# fb20-5.net
KiCad netlist of a schematic drawn in EAGLE
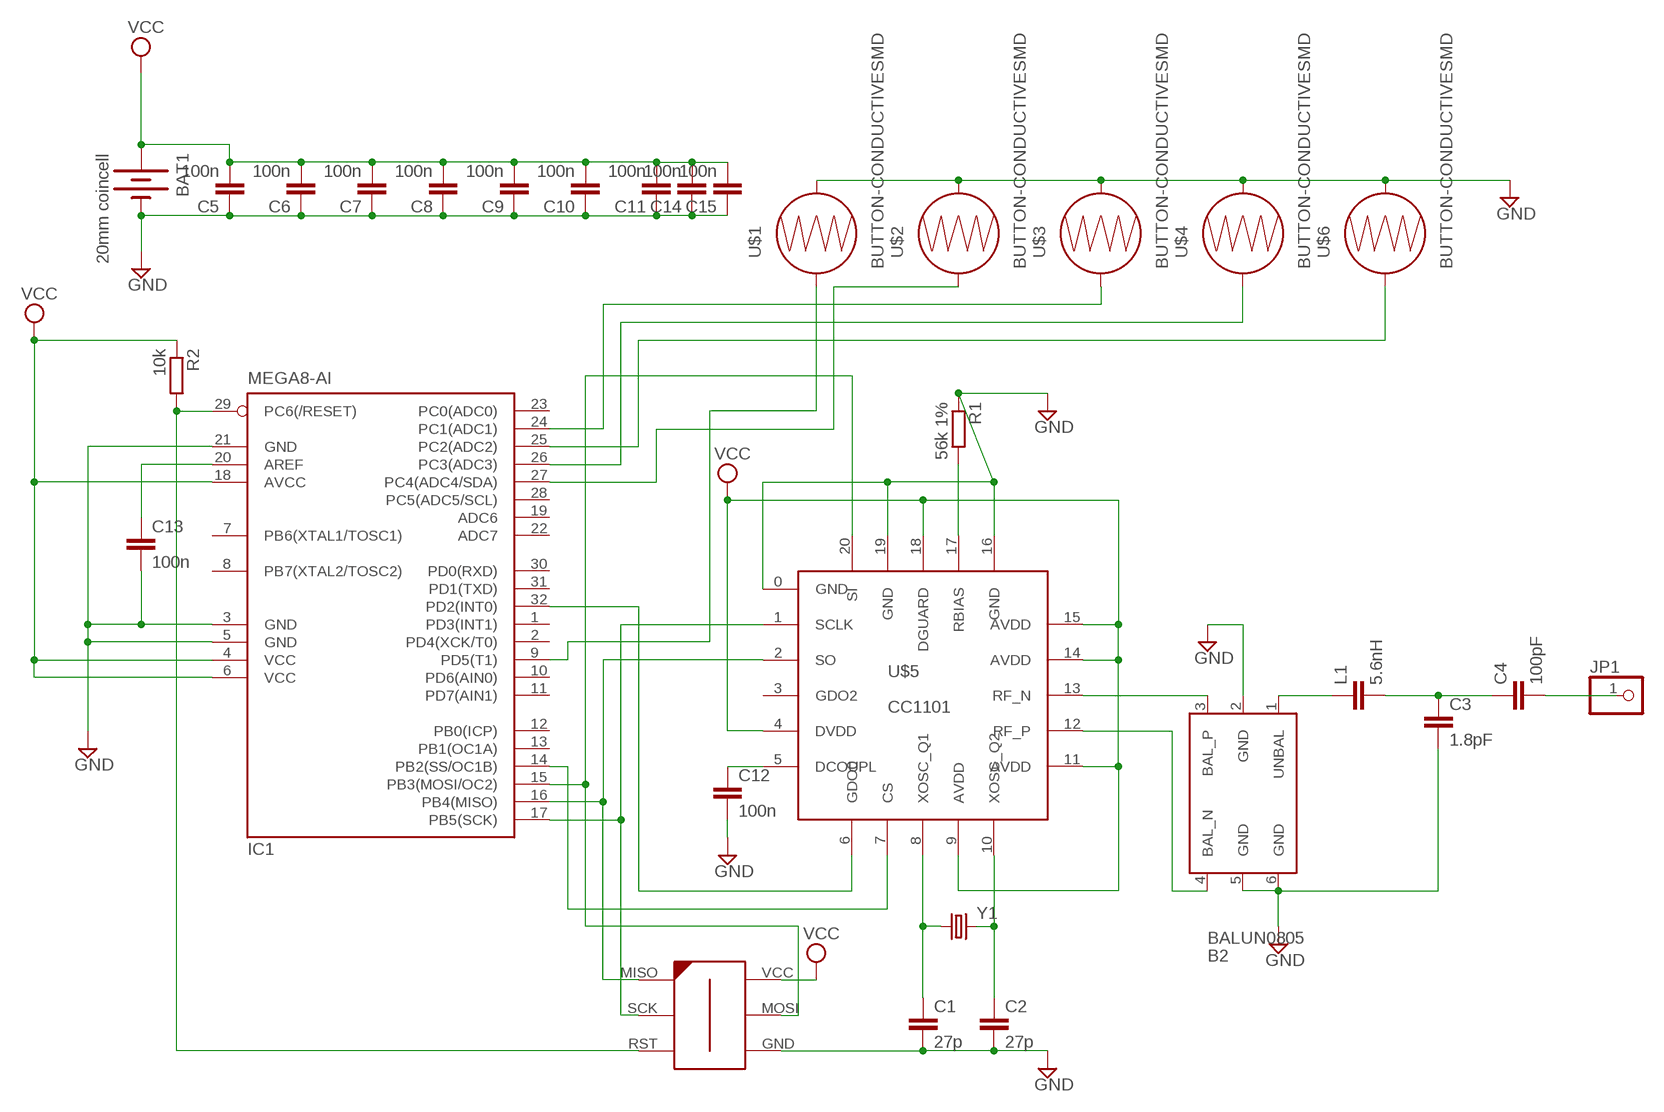
[diagram p0: schematic, sheet 1]

(export (version "E")
  (design (tool "Eeschema 10.0.6"))
  (components
    (comp (ref "B2")
      (value "BALUN0805")
      (footprint "eagle-import:BALUN")
      (libsource (lib "eagle-import") (part "BALUN0805"))
    )
    (comp (ref "BAT1")
      (value "20mm coincell")
      (footprint "eagle-import:BATTCON_20MM_4LEGS")
      (libsource (lib "eagle-import") (part "BATTERY20MM_4LEGS"))
    )
    (comp (ref "C1")
      (value "27p")
      (footprint "eagle-import:C0402")
      (libsource (lib "eagle-import") (part "C-EUC0402"))
    )
    (comp (ref "C2")
      (value "27p")
      (footprint "eagle-import:C0402")
      (libsource (lib "eagle-import") (part "C-EUC0402"))
    )
    (comp (ref "C3")
      (value "1.8pF")
      (footprint "eagle-import:C0402")
      (libsource (lib "eagle-import") (part "C-EUC0402"))
    )
    (comp (ref "C4")
      (value "100pF")
      (footprint "eagle-import:C0402")
      (libsource (lib "eagle-import") (part "C-EUC0402"))
    )
    (comp (ref "C5")
      (value "100n")
      (footprint "eagle-import:C0402")
      (libsource (lib "eagle-import") (part "C-EUC0402"))
    )
    (comp (ref "C6")
      (value "100n")
      (footprint "eagle-import:C0402")
      (libsource (lib "eagle-import") (part "C-EUC0402"))
    )
    (comp (ref "C7")
      (value "100n")
      (footprint "eagle-import:C0402")
      (libsource (lib "eagle-import") (part "C-EUC0402"))
    )
    (comp (ref "C8")
      (value "100n")
      (footprint "eagle-import:C0402")
      (libsource (lib "eagle-import") (part "C-EUC0402"))
    )
    (comp (ref "C9")
      (value "100n")
      (footprint "eagle-import:C0402")
      (libsource (lib "eagle-import") (part "C-EUC0402"))
    )
    (comp (ref "C10")
      (value "100n")
      (footprint "eagle-import:C0402")
      (libsource (lib "eagle-import") (part "C-EUC0402"))
    )
    (comp (ref "C11")
      (value "100n")
      (footprint "eagle-import:C0402")
      (libsource (lib "eagle-import") (part "C-EUC0402"))
    )
    (comp (ref "C12")
      (value "100n")
      (footprint "eagle-import:C0402")
      (libsource (lib "eagle-import") (part "C-EUC0402"))
    )
    (comp (ref "C13")
      (value "100n")
      (footprint "eagle-import:C0402")
      (libsource (lib "eagle-import") (part "C-EUC0402"))
    )
    (comp (ref "C14")
      (value "100n")
      (footprint "eagle-import:C0402")
      (libsource (lib "eagle-import") (part "C-EUC0402"))
    )
    (comp (ref "C15")
      (value "100n")
      (footprint "eagle-import:C0402")
      (libsource (lib "eagle-import") (part "C-EUC0402"))
    )
    (comp (ref "IC1")
      (value "MEGA8-AI")
      (footprint "eagle-import:TQFP32-08")
      (fields (field (name "MPN") "ATMEGA8-16AU"))
      (libsource (lib "eagle-import") (part "MEGA8-AI"))
    )
    (comp (ref "JP1")
      (value "PINHD-1X1")
      (footprint "eagle-import:1X01")
      (libsource (lib "eagle-import") (part "PINHD-1X1"))
    )
    (comp (ref "L1")
      (value "5.6nH")
      (footprint "eagle-import:C0603")
      (libsource (lib "eagle-import") (part "C-EUC0603"))
    )
    (comp (ref "R1")
      (value "56k 1%")
      (footprint "eagle-import:R0402")
      (libsource (lib "eagle-import") (part "R-EU_R0402"))
    )
    (comp (ref "R2")
      (value "10k")
      (footprint "eagle-import:R0402")
      (libsource (lib "eagle-import") (part "R-EU_R0402"))
    )
    (comp (ref "U$1")
      (value "BUTTON-CONDUCTIVESMD")
      (footprint "eagle-import:BUTTON-CONDUCTIVE")
      (libsource (lib "eagle-import") (part "BUTTON-CONDUCTIVESMD"))
    )
    (comp (ref "U$2")
      (value "BUTTON-CONDUCTIVESMD")
      (footprint "eagle-import:BUTTON-CONDUCTIVE")
      (libsource (lib "eagle-import") (part "BUTTON-CONDUCTIVESMD"))
    )
    (comp (ref "U$3")
      (value "BUTTON-CONDUCTIVESMD")
      (footprint "eagle-import:BUTTON-CONDUCTIVE")
      (libsource (lib "eagle-import") (part "BUTTON-CONDUCTIVESMD"))
    )
    (comp (ref "U$4")
      (value "BUTTON-CONDUCTIVESMD")
      (footprint "eagle-import:BUTTON-CONDUCTIVE")
      (libsource (lib "eagle-import") (part "BUTTON-CONDUCTIVESMD"))
    )
    (comp (ref "U$5")
      (value "CC1101")
      (footprint "eagle-import:QFN20")
      (libsource (lib "eagle-import") (part "CC1101"))
    )
    (comp (ref "U$6")
      (value "BUTTON-CONDUCTIVESMD")
      (footprint "eagle-import:BUTTON-CONDUCTIVE")
      (libsource (lib "eagle-import") (part "BUTTON-CONDUCTIVESMD"))
    )
    (comp (ref "U$7")
      (value "AVR-ISP-6-EDGE")
      (footprint "eagle-import:6PAD_ISP")
      (libsource (lib "eagle-import") (part "AVR-ISP-6-EDGE"))
    )
    (comp (ref "Y1")
      (value "CRYSTAL5X3")
      (footprint "eagle-import:CRYSTAL-SMD-5X3")
      (libsource (lib "eagle-import") (part "CRYSTAL5X3"))
    )
  )
  (nets
    (net (code "1") (name "GND") (class "Default")
      (node (ref "B2") (pin "2") (pinfunction "GND_2") (pintype "bidirectional"))
      (node (ref "B2") (pin "5") (pinfunction "GND_5") (pintype "bidirectional"))
      (node (ref "B2") (pin "6") (pinfunction "GND_6") (pintype "bidirectional"))
      (node (ref "BAT1") (pin "2") (pinfunction "-_2") (pintype "power_in"))
      (node (ref "C1") (pin "2") (pinfunction "2_2") (pintype "passive"))
      (node (ref "C10") (pin "1") (pinfunction "1_1") (pintype "passive"))
      (node (ref "C11") (pin "1") (pinfunction "1_1") (pintype "passive"))
      (node (ref "C12") (pin "2") (pinfunction "2_2") (pintype "passive"))
      (node (ref "C13") (pin "2") (pinfunction "2_2") (pintype "passive"))
      (node (ref "C14") (pin "1") (pinfunction "1_1") (pintype "passive"))
      (node (ref "C15") (pin "1") (pinfunction "1_1") (pintype "passive"))
      (node (ref "C2") (pin "2") (pinfunction "2_2") (pintype "passive"))
      (node (ref "C3") (pin "2") (pinfunction "2_2") (pintype "passive"))
      (node (ref "C5") (pin "1") (pinfunction "1_1") (pintype "passive"))
      (node (ref "C6") (pin "1") (pinfunction "1_1") (pintype "passive"))
      (node (ref "C7") (pin "1") (pinfunction "1_1") (pintype "passive"))
      (node (ref "C8") (pin "1") (pinfunction "1_1") (pintype "passive"))
      (node (ref "C9") (pin "1") (pinfunction "1_1") (pintype "passive"))
      (node (ref "IC1") (pin "21") (pinfunction "GND_21") (pintype "power_in"))
      (node (ref "IC1") (pin "3") (pinfunction "GND_3") (pintype "power_in"))
      (node (ref "IC1") (pin "5") (pinfunction "GND_5") (pintype "power_in"))
      (node (ref "R1") (pin "1") (pinfunction "1_1") (pintype "passive"))
      (node (ref "U$1") (pin "2") (pinfunction "2_2") (pintype "passive"))
      (node (ref "U$2") (pin "2") (pinfunction "2_2") (pintype "passive"))
      (node (ref "U$3") (pin "2") (pinfunction "2_2") (pintype "passive"))
      (node (ref "U$4") (pin "2") (pinfunction "2_2") (pintype "passive"))
      (node (ref "U$5") (pin "0") (pinfunction "GND_0") (pintype "bidirectional"))
      (node (ref "U$5") (pin "16") (pinfunction "GND_16") (pintype "bidirectional"))
      (node (ref "U$5") (pin "19") (pinfunction "GND_19") (pintype "bidirectional"))
      (node (ref "U$6") (pin "2") (pinfunction "2_2") (pintype "passive"))
      (node (ref "U$7") (pin "GND") (pinfunction "P$4_GND") (pintype "bidirectional"))
    )
    (net (code "2") (name "Net-(B2-BAL_N)") (class "Default")
      (node (ref "B2") (pin "4") (pinfunction "BAL_N_4") (pintype "bidirectional"))
      (node (ref "U$5") (pin "12") (pinfunction "RF_P_12") (pintype "bidirectional"))
    )
    (net (code "3") (name "Net-(B2-BAL_P)") (class "Default")
      (node (ref "B2") (pin "3") (pinfunction "BAL_P_3") (pintype "bidirectional"))
      (node (ref "U$5") (pin "13") (pinfunction "RF_N_13") (pintype "bidirectional"))
    )
    (net (code "4") (name "Net-(B2-UNBAL)") (class "Default")
      (node (ref "B2") (pin "1") (pinfunction "UNBAL_1") (pintype "bidirectional"))
      (node (ref "L1") (pin "1") (pinfunction "1_1") (pintype "passive"))
    )
    (net (code "5") (name "Net-(C3-Pad1)") (class "Default")
      (node (ref "C3") (pin "1") (pinfunction "1_1") (pintype "passive"))
      (node (ref "C4") (pin "1") (pinfunction "1_1") (pintype "passive"))
      (node (ref "L1") (pin "2") (pinfunction "2_2") (pintype "passive"))
    )
    (net (code "6") (name "Net-(C4-Pad2)") (class "Default")
      (node (ref "C4") (pin "2") (pinfunction "2_2") (pintype "passive"))
      (node (ref "JP1") (pin "1") (pinfunction "1_1") (pintype "passive"))
    )
    (net (code "7") (name "Net-(IC1-AREF)") (class "Default")
      (node (ref "C13") (pin "1") (pinfunction "1_1") (pintype "passive"))
      (node (ref "IC1") (pin "20") (pinfunction "AREF_20") (pintype "passive"))
    )
    (net (code "8") (name "Net-(IC1-PB2(SS{slash}OC1B))") (class "Default")
      (node (ref "IC1") (pin "14") (pinfunction "PB2(SS/OC1B)_14") (pintype "bidirectional"))
      (node (ref "U$5") (pin "7") (pinfunction "CS_7") (pintype "bidirectional"))
    )
    (net (code "9") (name "Net-(IC1-PB3(MOSI{slash}OC2))") (class "Default")
      (node (ref "IC1") (pin "15") (pinfunction "PB3(MOSI/OC2)_15") (pintype "bidirectional"))
      (node (ref "U$5") (pin "20") (pinfunction "SI_20") (pintype "bidirectional"))
      (node (ref "U$7") (pin "MOSI") (pinfunction "P$5_MOSI") (pintype "bidirectional"))
    )
    (net (code "10") (name "Net-(IC1-PB4(MISO))") (class "Default")
      (node (ref "IC1") (pin "16") (pinfunction "PB4(MISO)_16") (pintype "bidirectional"))
      (node (ref "U$5") (pin "2") (pinfunction "SO_2") (pintype "bidirectional"))
      (node (ref "U$7") (pin "MISO") (pinfunction "P$1_MISO") (pintype "bidirectional"))
    )
    (net (code "11") (name "Net-(IC1-PB5(SCK))") (class "Default")
      (node (ref "IC1") (pin "17") (pinfunction "PB5(SCK)_17") (pintype "bidirectional"))
      (node (ref "U$5") (pin "1") (pinfunction "SCLK_1") (pintype "bidirectional"))
      (node (ref "U$7") (pin "SCK") (pinfunction "P$2_SCK") (pintype "bidirectional"))
    )
    (net (code "12") (name "Net-(IC1-PC1(ADC1))") (class "Default")
      (node (ref "IC1") (pin "24") (pinfunction "PC1(ADC1)_24") (pintype "bidirectional"))
      (node (ref "U$3") (pin "1") (pinfunction "1_1") (pintype "passive"))
    )
    (net (code "13") (name "Net-(IC1-PC2(ADC2))") (class "Default")
      (node (ref "IC1") (pin "25") (pinfunction "PC2(ADC2)_25") (pintype "bidirectional"))
      (node (ref "U$6") (pin "1") (pinfunction "1_1") (pintype "passive"))
    )
    (net (code "14") (name "Net-(IC1-PC3(ADC3))") (class "Default")
      (node (ref "IC1") (pin "26") (pinfunction "PC3(ADC3)_26") (pintype "bidirectional"))
      (node (ref "U$4") (pin "1") (pinfunction "1_1") (pintype "passive"))
    )
    (net (code "15") (name "Net-(IC1-PC4(ADC4{slash}SDA))") (class "Default")
      (node (ref "IC1") (pin "27") (pinfunction "PC4(ADC4/SDA)_27") (pintype "bidirectional"))
      (node (ref "U$2") (pin "1") (pinfunction "1_1") (pintype "passive"))
    )
    (net (code "16") (name "Net-(IC1-PC6({slash}RESET))") (class "Default")
      (node (ref "IC1") (pin "29") (pinfunction "PC6(/RESET)_29") (pintype "bidirectional"))
      (node (ref "R2") (pin "2") (pinfunction "2_2") (pintype "passive"))
      (node (ref "U$7") (pin "RST") (pinfunction "P$3_RST") (pintype "bidirectional"))
    )
    (net (code "17") (name "Net-(IC1-PD2(INT0))") (class "Default")
      (node (ref "IC1") (pin "32") (pinfunction "PD2(INT0)_32") (pintype "bidirectional"))
      (node (ref "U$5") (pin "6") (pinfunction "GDO0_6") (pintype "bidirectional"))
    )
    (net (code "18") (name "Net-(IC1-PD5(T1))") (class "Default")
      (node (ref "IC1") (pin "9") (pinfunction "PD5(T1)_9") (pintype "bidirectional"))
      (node (ref "U$1") (pin "1") (pinfunction "1_1") (pintype "passive"))
    )
    (net (code "19") (name "Net-(U$5-DCOUPL)") (class "Default")
      (node (ref "C12") (pin "1") (pinfunction "1_1") (pintype "passive"))
      (node (ref "U$5") (pin "5") (pinfunction "DCOUPL_5") (pintype "bidirectional"))
    )
    (net (code "20") (name "Net-(U$5-RBIAS)") (class "Default")
      (node (ref "R1") (pin "2") (pinfunction "2_2") (pintype "passive"))
      (node (ref "U$5") (pin "17") (pinfunction "RBIAS_17") (pintype "bidirectional"))
    )
    (net (code "21") (name "Net-(U$5-XOSC_Q1)") (class "Default")
      (node (ref "C1") (pin "1") (pinfunction "1_1") (pintype "passive"))
      (node (ref "U$5") (pin "8") (pinfunction "XOSC_Q1_8") (pintype "bidirectional"))
      (node (ref "Y1") (pin "1") (pinfunction "1_1") (pintype "passive"))
    )
    (net (code "22") (name "Net-(U$5-XOSC_Q2)") (class "Default")
      (node (ref "C2") (pin "1") (pinfunction "1_1") (pintype "passive"))
      (node (ref "U$5") (pin "10") (pinfunction "XOSC_Q2_10") (pintype "bidirectional"))
      (node (ref "Y1") (pin "3") (pinfunction "2_3") (pintype "passive"))
    )
    (net (code "23") (name "VCC") (class "Default")
      (node (ref "BAT1") (pin "1") (pinfunction "+_1") (pintype "power_in"))
      (node (ref "C10") (pin "2") (pinfunction "2_2") (pintype "passive"))
      (node (ref "C11") (pin "2") (pinfunction "2_2") (pintype "passive"))
      (node (ref "C14") (pin "2") (pinfunction "2_2") (pintype "passive"))
      (node (ref "C15") (pin "2") (pinfunction "2_2") (pintype "passive"))
      (node (ref "C5") (pin "2") (pinfunction "2_2") (pintype "passive"))
      (node (ref "C6") (pin "2") (pinfunction "2_2") (pintype "passive"))
      (node (ref "C7") (pin "2") (pinfunction "2_2") (pintype "passive"))
      (node (ref "C8") (pin "2") (pinfunction "2_2") (pintype "passive"))
      (node (ref "C9") (pin "2") (pinfunction "2_2") (pintype "passive"))
      (node (ref "IC1") (pin "18") (pinfunction "AVCC_18") (pintype "power_in"))
      (node (ref "IC1") (pin "4") (pinfunction "VCC_4") (pintype "power_in"))
      (node (ref "IC1") (pin "6") (pinfunction "VCC_6") (pintype "power_in"))
      (node (ref "R2") (pin "1") (pinfunction "1_1") (pintype "passive"))
      (node (ref "U$5") (pin "11") (pinfunction "AVDD_11") (pintype "bidirectional"))
      (node (ref "U$5") (pin "14") (pinfunction "AVDD_14") (pintype "bidirectional"))
      (node (ref "U$5") (pin "15") (pinfunction "AVDD_15") (pintype "bidirectional"))
      (node (ref "U$5") (pin "18") (pinfunction "DGUARD_18") (pintype "bidirectional"))
      (node (ref "U$5") (pin "4") (pinfunction "DVDD_4") (pintype "bidirectional"))
      (node (ref "U$5") (pin "9") (pinfunction "AVDD_9") (pintype "bidirectional"))
      (node (ref "U$7") (pin "VCC") (pinfunction "P$6_VCC") (pintype "bidirectional"))
    )
    (net (code "24") (name "unconnected-(IC1-ADC6-Pad19)") (class "Default")
      (node (ref "IC1") (pin "19") (pinfunction "ADC6_19") (pintype "bidirectional"))
    )
    (net (code "25") (name "unconnected-(IC1-ADC7-Pad22)") (class "Default")
      (node (ref "IC1") (pin "22") (pinfunction "ADC7_22") (pintype "bidirectional"))
    )
    (net (code "26") (name "unconnected-(IC1-PB0(ICP)-Pad12)") (class "Default")
      (node (ref "IC1") (pin "12") (pinfunction "PB0(ICP)_12") (pintype "bidirectional"))
    )
    (net (code "27") (name "unconnected-(IC1-PB1(OC1A)-Pad13)") (class "Default")
      (node (ref "IC1") (pin "13") (pinfunction "PB1(OC1A)_13") (pintype "bidirectional"))
    )
    (net (code "28") (name "unconnected-(IC1-PB6(XTAL1{slash}TOSC1)-Pad7)") (class "Default")
      (node (ref "IC1") (pin "7") (pinfunction "PB6(XTAL1/TOSC1)_7") (pintype "bidirectional"))
    )
    (net (code "29") (name "unconnected-(IC1-PB7(XTAL2{slash}TOSC2)-Pad8)") (class "Default")
      (node (ref "IC1") (pin "8") (pinfunction "PB7(XTAL2/TOSC2)_8") (pintype "bidirectional"))
    )
    (net (code "30") (name "unconnected-(IC1-PC0(ADC0)-Pad23)") (class "Default")
      (node (ref "IC1") (pin "23") (pinfunction "PC0(ADC0)_23") (pintype "bidirectional"))
    )
    (net (code "31") (name "unconnected-(IC1-PC5(ADC5{slash}SCL)-Pad28)") (class "Default")
      (node (ref "IC1") (pin "28") (pinfunction "PC5(ADC5/SCL)_28") (pintype "bidirectional"))
    )
    (net (code "32") (name "unconnected-(IC1-PD0(RXD)-Pad30)") (class "Default")
      (node (ref "IC1") (pin "30") (pinfunction "PD0(RXD)_30") (pintype "bidirectional"))
    )
    (net (code "33") (name "unconnected-(IC1-PD1(TXD)-Pad31)") (class "Default")
      (node (ref "IC1") (pin "31") (pinfunction "PD1(TXD)_31") (pintype "bidirectional"))
    )
    (net (code "34") (name "unconnected-(IC1-PD3(INT1)-Pad1)") (class "Default")
      (node (ref "IC1") (pin "1") (pinfunction "PD3(INT1)_1") (pintype "bidirectional"))
    )
    (net (code "35") (name "unconnected-(IC1-PD4(XCK{slash}T0)-Pad2)") (class "Default")
      (node (ref "IC1") (pin "2") (pinfunction "PD4(XCK/T0)_2") (pintype "bidirectional"))
    )
    (net (code "36") (name "unconnected-(IC1-PD6(AIN0)-Pad10)") (class "Default")
      (node (ref "IC1") (pin "10") (pinfunction "PD6(AIN0)_10") (pintype "bidirectional"))
    )
    (net (code "37") (name "unconnected-(IC1-PD7(AIN1)-Pad11)") (class "Default")
      (node (ref "IC1") (pin "11") (pinfunction "PD7(AIN1)_11") (pintype "bidirectional"))
    )
    (net (code "38") (name "unconnected-(U$5-GDO2-Pad3)") (class "Default")
      (node (ref "U$5") (pin "3") (pinfunction "GDO2_3") (pintype "bidirectional"))
    )
  )
)
